# USBC.net
KiCad netlist of a schematic drawn in Altium Designer
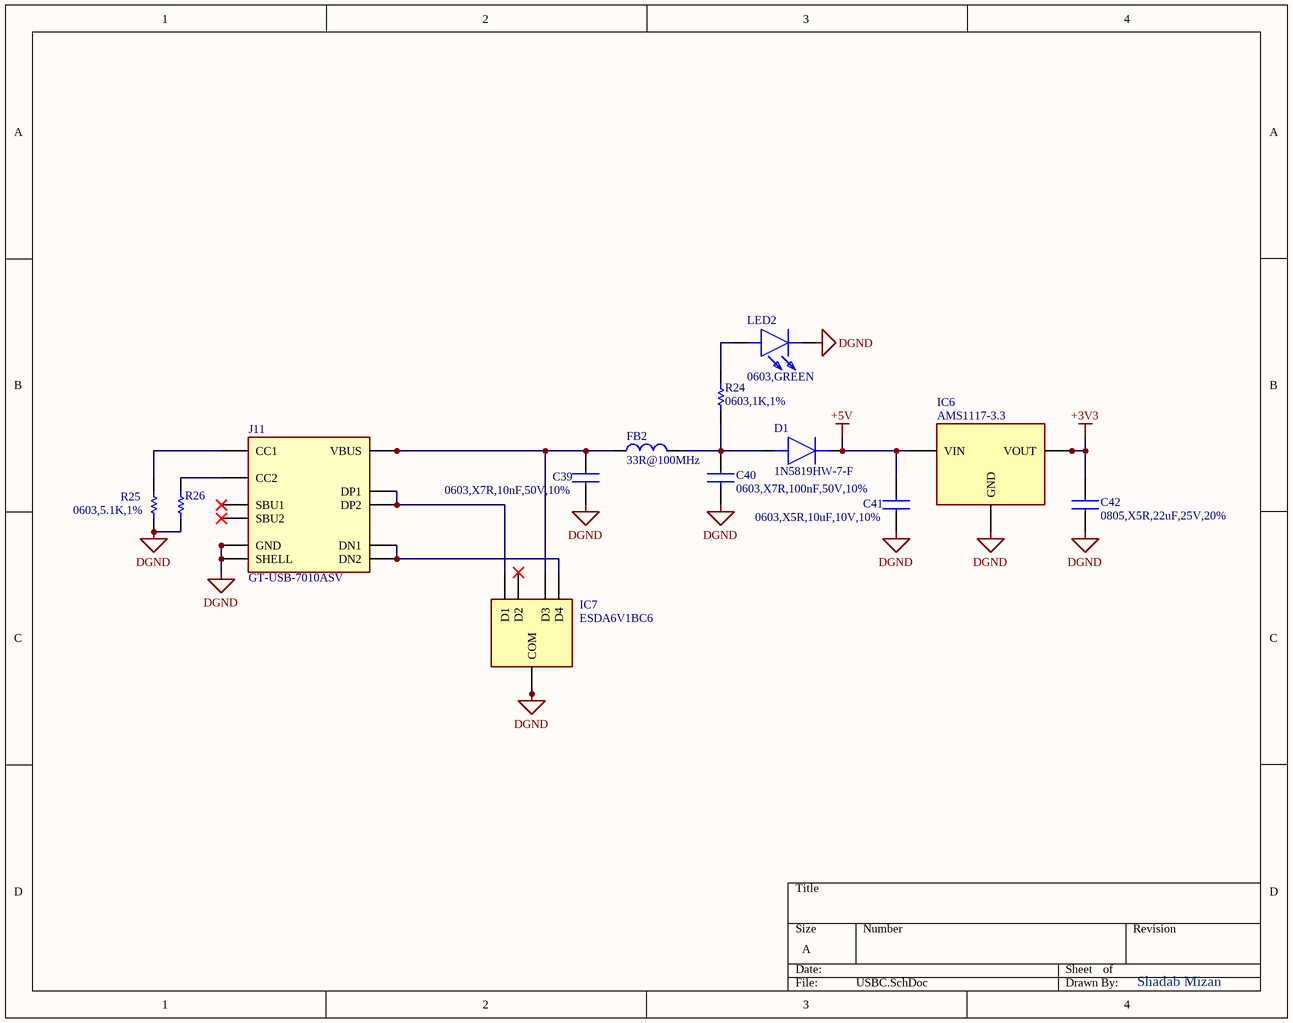
[diagram p0: USBC.SchDoc]

(export (version "E")
  (design (tool "Eeschema 10.0.6"))
  (components
    (comp (ref "C39")
      (value "0603,X7R,10nF,50V,10%")
      (footprint "CAPC1608X90N")
      (description "10nF ±10% 50V Ceramic Capacitor X7R 0603")
      (fields (field (name "LCSC PART #") "C57112") (field (name "MANU PART #") "0603B103K500NT"))
      (libsource (lib "flight-controller") (part "0603B103K500NT"))
    )
    (comp (ref "C40")
      (value "0603,X7R,100nF,50V,10%")
      (footprint "CAPC1608X90N")
      (description "50V 100nF X7R ±10% 0603 Multilayer Ceramic Capacitors MLCC - SMD/SMT ROHS")
      (fields (field (name "LCSC PART #") "C14663") (field (name "MANU PART #") "CC0603KRX7R9BB104"))
      (libsource (lib "flight-controller") (part "CC0603KRX7R9BB104"))
    )
    (comp (ref "C41")
      (value "0603,X5R,10uF,10V,10%")
      (footprint "CAPC1608X90N")
      (description "10uF ±10% 10V Ceramic Capacitor X5R 0603")
      (fields (field (name "LCSC PART #") "C19702") (field (name "MANU PART #") "CL10A106KP8NNNC"))
      (libsource (lib "flight-controller") (part "CL10A106KP8NNNC"))
    )
    (comp (ref "C42")
      (value "0805,X5R,22uF,25V,20%")
      (footprint "CAPC2012X145N")
      (description "22uF ±20% 25V Ceramic Capacitor X5R 0805")
      (fields (field (name "LCSC PART #") "C45783") (field (name "MANU PART #") "CL21A226MAQNNNE"))
      (libsource (lib "flight-controller") (part "CL21A226MAQNNNE"))
    )
    (comp (ref "D1")
      (value "1N5819HW-7-F")
      (footprint "SOD3716X125N")
      (description "25A 1 Independent 40V 450mV@1A 1A SOD-123 Single Diodes RoHS")
      (fields (field (name "LCSC PART #") "C82544"))
      (libsource (lib "flight-controller") (part "1N5819HW-7-F"))
    )
    (comp (ref "FB2")
      (value "33R@100MHz")
      (footprint "BLM18SP221SN1B")
      (description "33Ω@100MHz 1 Line Ferrite Bead 0603 6A 8mΩ")
      (fields (field (name "MANU PART #") "BLM18SG330SN1D") (field (name "LCSC PART #") "C576399"))
      (libsource (lib "flight-controller") (part "BLM18SG330SN1D"))
    )
    (comp (ref "IC6")
      (value "AMS1117-3.3")
      (footprint "SOT230P700X180-4N")
      (fields (field (name "LCSC PART #") "C6186"))
      (libsource (lib "flight-controller") (part "AMS1117-3.3"))
    )
    (comp (ref "IC7")
      (value "ESDA6V1BC6")
      (footprint "SOT95P280X145-6N")
      (description "Clamp Ipp Tvs Diode Surface Mount SOT-23-6")
      (fields (field (name "LCSC PART #") "C495220"))
      (libsource (lib "flight-controller") (part "ESDA6V1BC6"))
    )
    (comp (ref "J11")
      (value "GT-USB-7010ASV")
      (footprint "USB-C-SMD_G-SWITCH_GT-USB-7010ASV")
      (description "USB 2.0 3A 1 Surface Mount, Right Angle 16P Female -40℃~+85℃ Type-C SMD USB Connectors ROHS")
      (fields (field (name "LCSC PART #") "C2988369"))
      (libsource (lib "flight-controller") (part "GT-USB-7010ASV"))
    )
    (comp (ref "LED2")
      (value "0603,GREEN")
      (footprint "LEDC1608X36N")
      (description "Green LED Indication - Discrete 2.2V 0603")
      (fields (field (name "MANU PART #") "SML-E12P8WT86") (field (name "LCSC PART #") "C126319"))
      (libsource (lib "flight-controller") (part "SML-E12P8WT86"))
    )
    (comp (ref "R24")
      (value "0603,1K,1%")
      (footprint "RESC1608X90N")
      (description "100mW 1kΩ 75V Thick Film Resistor ±100ppm/℃ ±1% 0603 Chip Resistor - Surface Mount RoHS")
      (fields (field (name "LCSC PART #") "C21190") (field (name "MANU PART #") "0603WAF1001T5E"))
      (libsource (lib "flight-controller") (part "0603WAF1001T5E"))
    )
    (comp (ref "R25")
      (value "0603,5.1K,1%")
      (footprint "RESC1608X55N")
      (description "100mW 5.1kΩ 75V Thick Film Resistor ±100ppm/℃ ±1% 0603 Chip Resistor - Surface Mount RoHS")
      (fields (field (name "LCSC PART #") "C105580") (field (name "MANU PART #") "RC0603FR-075K1L"))
      (libsource (lib "flight-controller") (part "RC0603FR-075K1L"))
    )
    (comp (ref "R26")
      (value "0603,5.1K,1%")
      (footprint "RESC1608X55N")
      (description "100mW 5.1kΩ 75V Thick Film Resistor ±100ppm/℃ ±1% 0603 Chip Resistor - Surface Mount RoHS")
      (fields (field (name "LCSC PART #") "C105580") (field (name "MANU PART #") "RC0603FR-075K1L"))
      (libsource (lib "flight-controller") (part "RC0603FR-075K1L"))
    )
  )
  (nets
    (net (code "1") (name "+3V3") (class "Default")
      (node (ref "C42") (pin "2") (pinfunction "2_2") (pintype "passive"))
      (node (ref "IC6") (pin "2") (pinfunction "OUTPUT_2") (pintype "passive"))
      (node (ref "IC6") (pin "4") (pinfunction "VOUT_4") (pintype "passive"))
    )
    (net (code "2") (name "+5V") (class "Default")
      (node (ref "C41") (pin "2") (pinfunction "2_2") (pintype "passive"))
      (node (ref "D1") (pin "1") (pinfunction "K_1") (pintype "passive"))
      (node (ref "IC6") (pin "3") (pinfunction "VIN_3") (pintype "passive"))
    )
    (net (code "3") (name "DGND") (class "Default")
      (node (ref "C39") (pin "1") (pinfunction "1_1") (pintype "passive"))
      (node (ref "C40") (pin "1") (pinfunction "1_1") (pintype "passive"))
      (node (ref "C41") (pin "1") (pinfunction "1_1") (pintype "passive"))
      (node (ref "C42") (pin "1") (pinfunction "1_1") (pintype "passive"))
      (node (ref "IC6") (pin "1") (pinfunction "GND_1") (pintype "passive"))
      (node (ref "IC7") (pin "2") (pinfunction "COM_2") (pintype "passive"))
      (node (ref "IC7") (pin "5") (pinfunction "COM_5") (pintype "passive"))
      (node (ref "J11") (pin "1") (pinfunction "SHELL_1") (pintype "passive"))
      (node (ref "J11") (pin "2") (pinfunction "SHELL_2") (pintype "passive"))
      (node (ref "J11") (pin "3") (pinfunction "SHELL_3") (pintype "passive"))
      (node (ref "J11") (pin "4") (pinfunction "SHELL_4") (pintype "passive"))
      (node (ref "J11") (pin "A1B12") (pinfunction "GND_A1B12") (pintype "passive"))
      (node (ref "J11") (pin "B1A12") (pinfunction "GND_B1A12") (pintype "passive"))
      (node (ref "LED2") (pin "1") (pinfunction "K_1") (pintype "passive"))
      (node (ref "R25") (pin "2") (pinfunction "2_2") (pintype "passive"))
      (node (ref "R26") (pin "2") (pinfunction "2_2") (pintype "passive"))
    )
    (net (code "4") (name "Net-(D1-A)") (class "Default")
      (node (ref "C40") (pin "2") (pinfunction "2_2") (pintype "passive"))
      (node (ref "D1") (pin "2") (pinfunction "A_2") (pintype "passive"))
      (node (ref "FB2") (pin "2") (pinfunction "2_2") (pintype "passive"))
      (node (ref "R24") (pin "1") (pinfunction "1_1") (pintype "passive"))
    )
    (net (code "5") (name "Net-(IC7-D1)") (class "Default")
      (node (ref "IC7") (pin "1") (pinfunction "D1_1") (pintype "passive"))
      (node (ref "J11") (pin "A6") (pinfunction "DP1_A6") (pintype "passive"))
      (node (ref "J11") (pin "B6") (pinfunction "DP2_B6") (pintype "passive"))
    )
    (net (code "6") (name "Net-(IC7-D3)") (class "Default")
      (node (ref "C39") (pin "2") (pinfunction "2_2") (pintype "passive"))
      (node (ref "FB2") (pin "1") (pinfunction "1_1") (pintype "passive"))
      (node (ref "IC7") (pin "4") (pinfunction "D3_4") (pintype "passive"))
      (node (ref "J11") (pin "A4B9") (pinfunction "VBUS_A4B9") (pintype "passive"))
      (node (ref "J11") (pin "B4A9") (pinfunction "VBUS_B4A9") (pintype "passive"))
    )
    (net (code "7") (name "Net-(IC7-D4)") (class "Default")
      (node (ref "IC7") (pin "6") (pinfunction "D4_6") (pintype "passive"))
      (node (ref "J11") (pin "A7") (pinfunction "DN1_A7") (pintype "passive"))
      (node (ref "J11") (pin "B7") (pinfunction "DN2_B7") (pintype "passive"))
    )
    (net (code "8") (name "Net-(J11-CC1)") (class "Default")
      (node (ref "J11") (pin "A5") (pinfunction "CC1_A5") (pintype "passive"))
      (node (ref "R25") (pin "1") (pinfunction "1_1") (pintype "passive"))
    )
    (net (code "9") (name "Net-(J11-CC2)") (class "Default")
      (node (ref "J11") (pin "B5") (pinfunction "CC2_B5") (pintype "passive"))
      (node (ref "R26") (pin "1") (pinfunction "1_1") (pintype "passive"))
    )
    (net (code "10") (name "Net-(LED2-A)") (class "Default")
      (node (ref "LED2") (pin "2") (pinfunction "A_2") (pintype "passive"))
      (node (ref "R24") (pin "2") (pinfunction "2_2") (pintype "passive"))
    )
    (net (code "11") (name "unconnected-(IC7-D2-Pad3)") (class "Default")
      (node (ref "IC7") (pin "3") (pinfunction "D2_3") (pintype "passive+no_connect"))
    )
    (net (code "12") (name "unconnected-(J11-SBU1-PadA8)") (class "Default")
      (node (ref "J11") (pin "A8") (pinfunction "SBU1_A8") (pintype "passive+no_connect"))
    )
    (net (code "13") (name "unconnected-(J11-SBU2-PadB8)") (class "Default")
      (node (ref "J11") (pin "B8") (pinfunction "SBU2_B8") (pintype "passive+no_connect"))
    )
  )
)
